# SCH_stmsheild_2026-06-30.net
KiCad netlist of a schematic drawn in EasyEDA
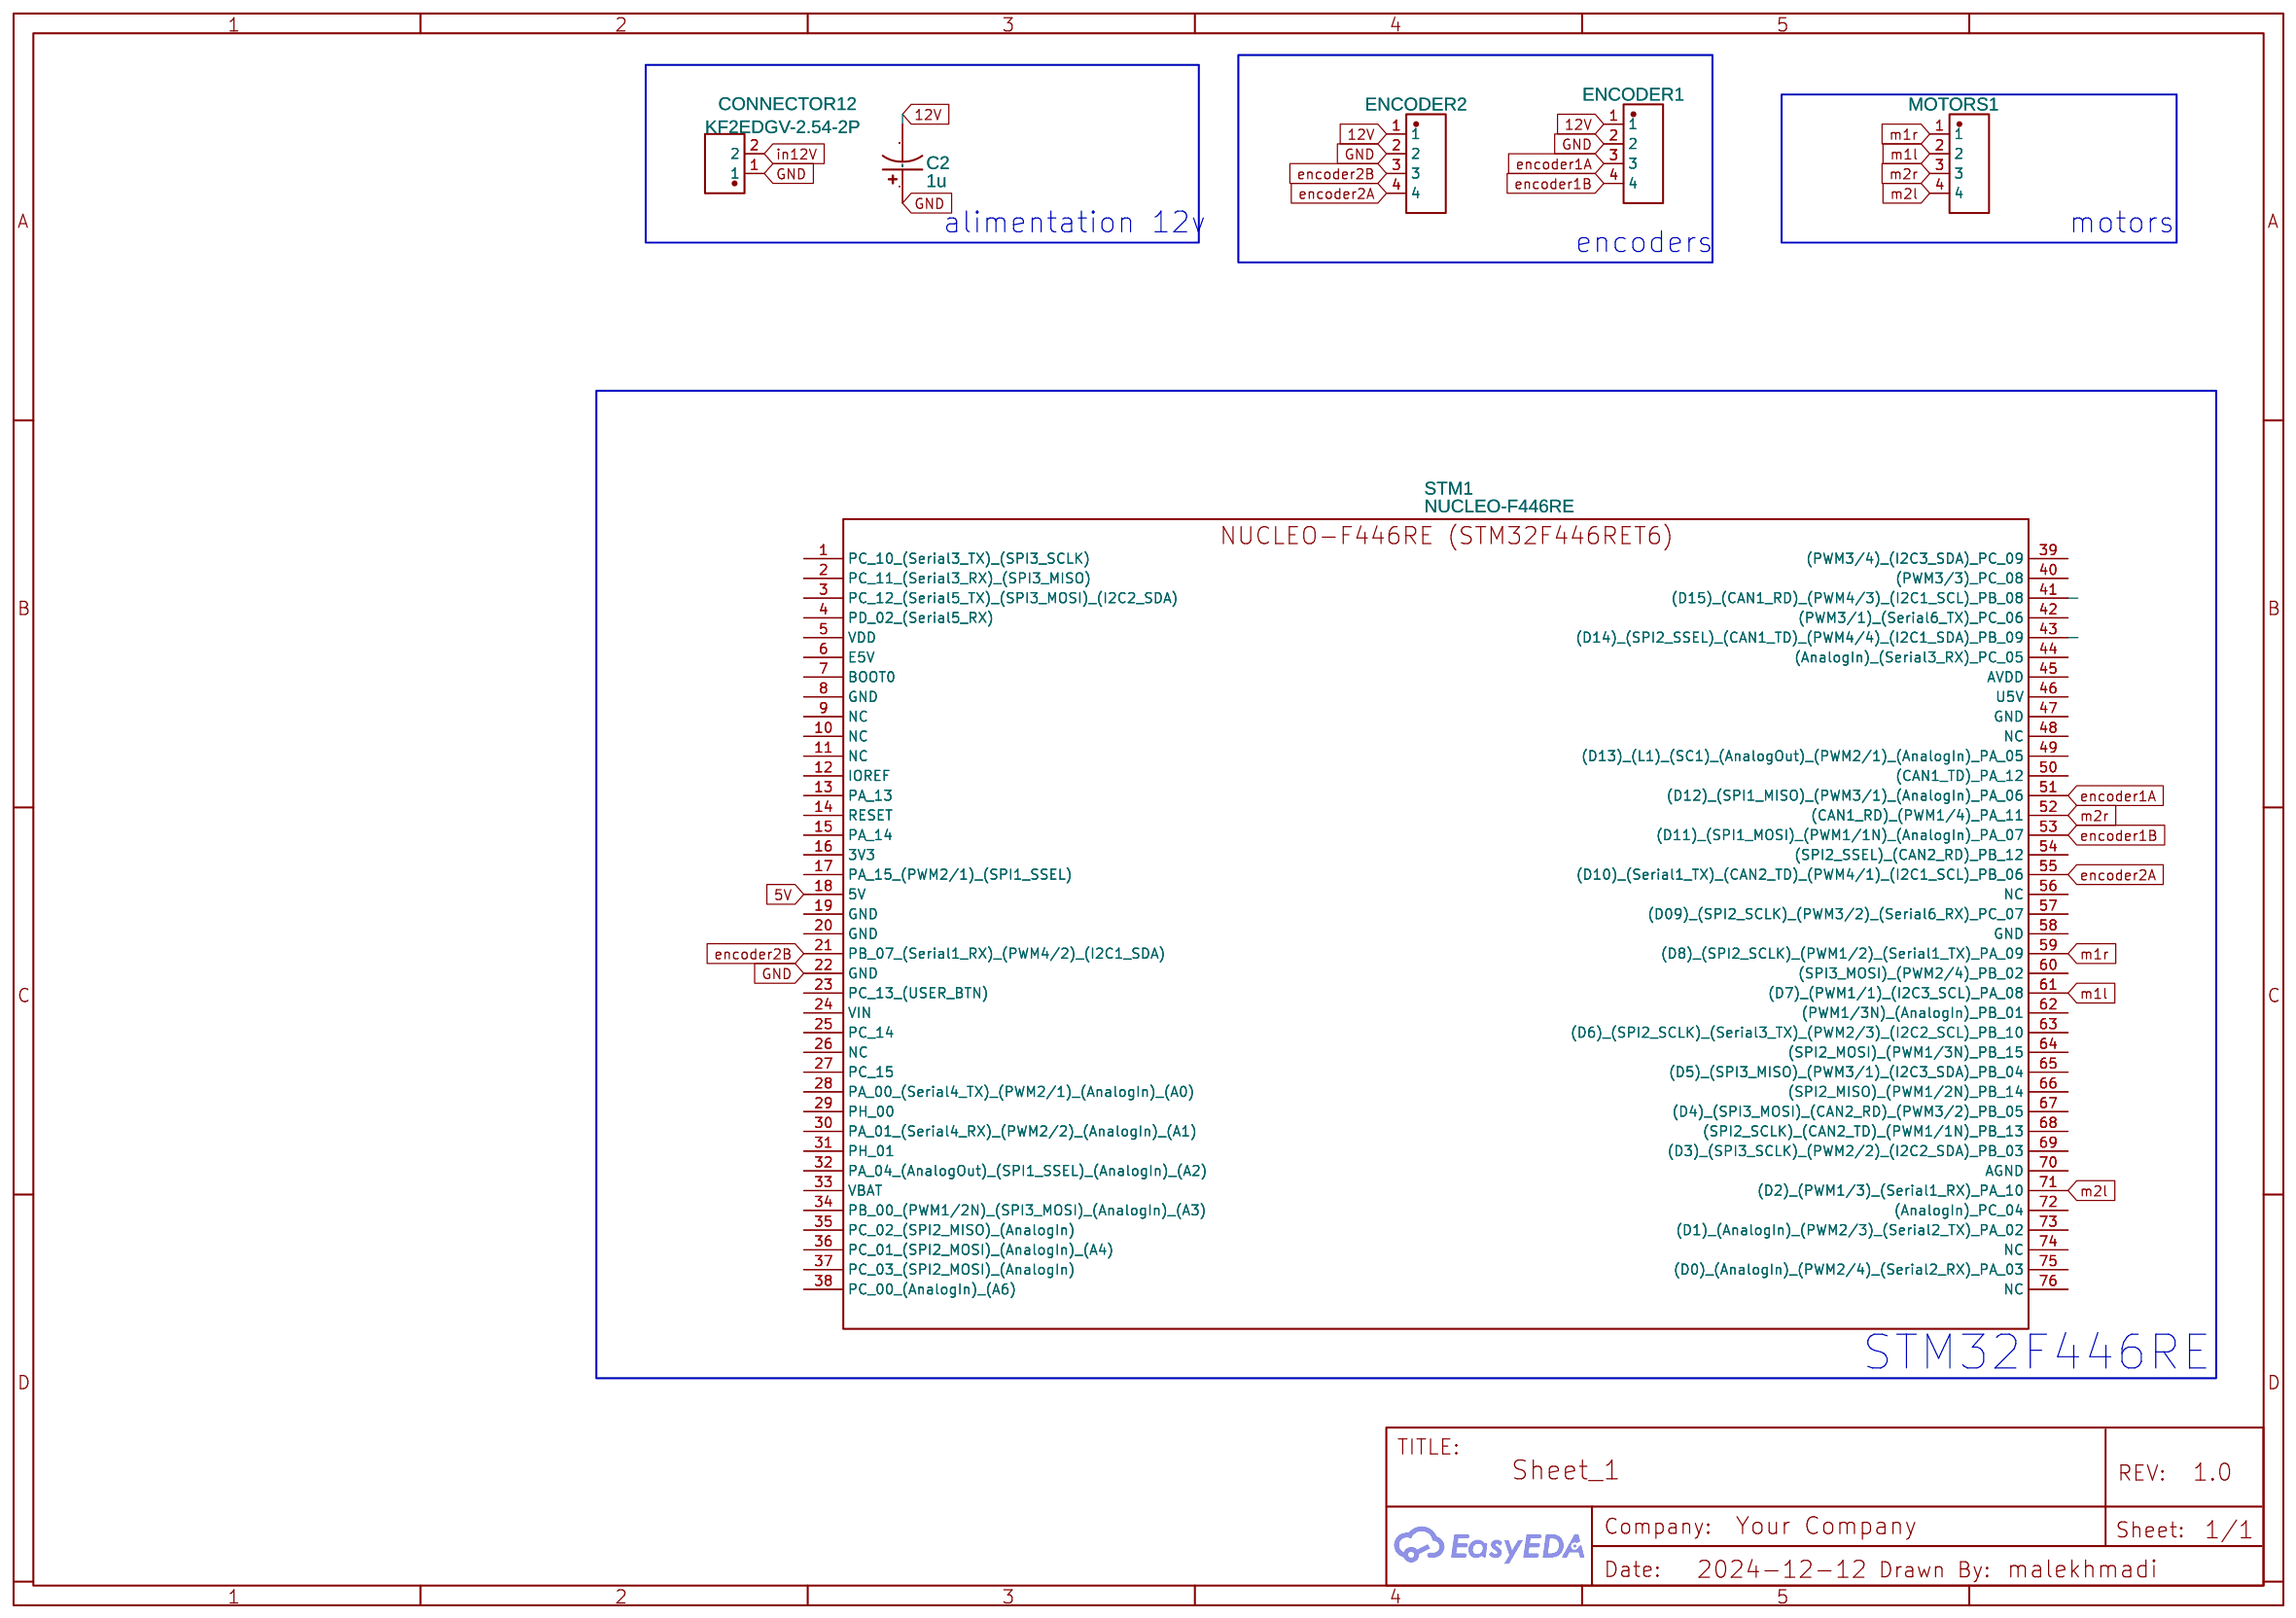
[diagram p0: schematic sheet]

(export (version "E")
  (design (tool "Eeschema 10.0.6"))
  (components
    (comp (ref "C2") (value "1u") (libsource (lib "") (part "CE_TH_D4.0×F1.5_US")))
    (comp (ref "CONNECTOR12")
      (value "KF2EDGV-2.54-2P")
      (fields (field (name "Manufacturer") "Cixi Kefa Elec"))
      (libsource (lib "") (part "KF2EDGV-2.54-2P"))
    )
    (comp (ref "ENCODER1")
      (value "HC-XHB-4A")
      (fields (field (name "Manufacturer") "HCTL(华灿天禄)"))
      (libsource (lib "") (part "HC-XHB-4A_1"))
    )
    (comp (ref "ENCODER2")
      (value "HC-XHB-4A")
      (fields (field (name "Manufacturer") "HCTL(华灿天禄)"))
      (libsource (lib "") (part "HC-XHB-4A_1"))
    )
    (comp (ref "MOTORS1")
      (value "HC-XHB-4A")
      (fields (field (name "Manufacturer") "HCTL(华灿天禄)"))
      (libsource (lib "") (part "HC-XHB-4A"))
    )
    (comp (ref "STM1") (value "NUCLEO-F446RE") (libsource (lib "") (part "NUCLEO-F446RE")))
  )
  (nets
    (net (code "1") (name "5V") (class "Default")
      (node (ref "STM1") (pin "18") (pinfunction "5V_18") (pintype "passive"))
    )
    (net (code "2") (name "12V") (class "Default")
      (node (ref "C2") (pin "2") (pinfunction "2_2") (pintype "unspecified"))
      (node (ref "ENCODER1") (pin "1") (pinfunction "1_1") (pintype "unspecified"))
      (node (ref "ENCODER2") (pin "1") (pinfunction "1_1") (pintype "unspecified"))
    )
    (net (code "3") (name "GND") (class "Default")
      (node (ref "C2") (pin "1") (pinfunction "1_1") (pintype "unspecified"))
      (node (ref "CONNECTOR12") (pin "1") (pinfunction "1_1") (pintype "unspecified"))
      (node (ref "ENCODER1") (pin "2") (pinfunction "2_2") (pintype "unspecified"))
      (node (ref "ENCODER2") (pin "2") (pinfunction "2_2") (pintype "unspecified"))
      (node (ref "STM1") (pin "22") (pinfunction "GND_22") (pintype "passive"))
    )
    (net (code "4") (name "encoder1A") (class "Default")
      (node (ref "ENCODER1") (pin "3") (pinfunction "3_3") (pintype "unspecified"))
      (node (ref "STM1") (pin "51") (pinfunction "(D12)_(SPI1_MISO)_(PWM3/1)_(AnalogIn)_PA_06_51") (pintype "bidirectional"))
    )
    (net (code "5") (name "encoder1B") (class "Default")
      (node (ref "ENCODER1") (pin "4") (pinfunction "4_4") (pintype "unspecified"))
      (node (ref "STM1") (pin "53") (pinfunction "(D11)_(SPI1_MOSI)_(PWM1/1N)_(AnalogIn)_PA_07_53") (pintype "bidirectional"))
    )
    (net (code "6") (name "encoder2A") (class "Default")
      (node (ref "ENCODER2") (pin "4") (pinfunction "4_4") (pintype "unspecified"))
      (node (ref "STM1") (pin "55") (pinfunction "(D10)_(Serial1_TX)_(CAN2_TD)_(PWM4/1)_(I2C1_SCL)_PB_06_55") (pintype "bidirectional"))
    )
    (net (code "7") (name "encoder2B") (class "Default")
      (node (ref "ENCODER2") (pin "3") (pinfunction "3_3") (pintype "unspecified"))
      (node (ref "STM1") (pin "21") (pinfunction "PB_07_(Serial1_RX)_(PWM4/2)_(I2C1_SDA)_21") (pintype "bidirectional"))
    )
    (net (code "8") (name "in12V") (class "Default")
      (node (ref "CONNECTOR12") (pin "2") (pinfunction "2_2") (pintype "unspecified"))
    )
    (net (code "9") (name "m1l") (class "Default")
      (node (ref "MOTORS1") (pin "2") (pinfunction "2_2") (pintype "unspecified"))
      (node (ref "STM1") (pin "61") (pinfunction "(D7)_(PWM1/1)_(I2C3_SCL)_PA_08_61") (pintype "bidirectional"))
    )
    (net (code "10") (name "m1r") (class "Default")
      (node (ref "MOTORS1") (pin "1") (pinfunction "1_1") (pintype "unspecified"))
      (node (ref "STM1") (pin "59") (pinfunction "(D8)_(SPI2_SCLK)_(PWM1/2)_(Serial1_TX)_PA_09_59") (pintype "bidirectional"))
    )
    (net (code "11") (name "m2l") (class "Default")
      (node (ref "MOTORS1") (pin "4") (pinfunction "4_4") (pintype "unspecified"))
      (node (ref "STM1") (pin "71") (pinfunction "(D2)_(PWM1/3)_(Serial1_RX)_PA_10_71") (pintype "bidirectional"))
    )
    (net (code "12") (name "m2r") (class "Default")
      (node (ref "MOTORS1") (pin "3") (pinfunction "3_3") (pintype "unspecified"))
      (node (ref "STM1") (pin "52") (pinfunction "(CAN1_RD)_(PWM1/4)_PA_11_52") (pintype "bidirectional"))
    )
    (net (code "13") (name "unconnected-(STM1-(AnalogIn)_(Serial3_RX)_PC_05-Pad44)") (class "Default")
      (node (ref "STM1") (pin "44") (pinfunction "(AnalogIn)_(Serial3_RX)_PC_05_44") (pintype "bidirectional"))
    )
    (net (code "14") (name "unconnected-(STM1-(AnalogIn)_PC_04-Pad72)") (class "Default")
      (node (ref "STM1") (pin "72") (pinfunction "(AnalogIn)_PC_04_72") (pintype "bidirectional"))
    )
    (net (code "15") (name "unconnected-(STM1-(CAN1_TD)_PA_12-Pad50)") (class "Default")
      (node (ref "STM1") (pin "50") (pinfunction "(CAN1_TD)_PA_12_50") (pintype "bidirectional"))
    )
    (net (code "16") (name "unconnected-(STM1-(D0)_(AnalogIn)_(PWM2{slash}4)_(Serial2_RX)_PA_03-Pad75)") (class "Default")
      (node (ref "STM1") (pin "75") (pinfunction "(D0)_(AnalogIn)_(PWM2/4)_(Serial2_RX)_PA_03_75") (pintype "bidirectional"))
    )
    (net (code "17") (name "unconnected-(STM1-(D1)_(AnalogIn)_(PWM2{slash}3)_(Serial2_TX)_PA_02-Pad73)") (class "Default")
      (node (ref "STM1") (pin "73") (pinfunction "(D1)_(AnalogIn)_(PWM2/3)_(Serial2_TX)_PA_02_73") (pintype "bidirectional"))
    )
    (net (code "18") (name "unconnected-(STM1-(D3)_(SPI3_SCLK)_(PWM2{slash}2)_(I2C2_SDA)_PB_03-Pad69)") (class "Default")
      (node (ref "STM1") (pin "69") (pinfunction "(D3)_(SPI3_SCLK)_(PWM2/2)_(I2C2_SDA)_PB_03_69") (pintype "bidirectional"))
    )
    (net (code "19") (name "unconnected-(STM1-(D4)_(SPI3_MOSI)_(CAN2_RD)_(PWM3{slash}2)_PB_05-Pad67)") (class "Default")
      (node (ref "STM1") (pin "67") (pinfunction "(D4)_(SPI3_MOSI)_(CAN2_RD)_(PWM3/2)_PB_05_67") (pintype "bidirectional"))
    )
    (net (code "20") (name "unconnected-(STM1-(D5)_(SPI3_MISO)_(PWM3{slash}1)_(I2C3_SDA)_PB_04-Pad65)") (class "Default")
      (node (ref "STM1") (pin "65") (pinfunction "(D5)_(SPI3_MISO)_(PWM3/1)_(I2C3_SDA)_PB_04_65") (pintype "bidirectional"))
    )
    (net (code "21") (name "unconnected-(STM1-(D6)_(SPI2_SCLK)_(Serial3_TX)_(PWM2{slash}3)_(I2C2_SCL)_PB_10-Pad63)") (class "Default")
      (node (ref "STM1") (pin "63") (pinfunction "(D6)_(SPI2_SCLK)_(Serial3_TX)_(PWM2/3)_(I2C2_SCL)_PB_10_63") (pintype "bidirectional"))
    )
    (net (code "22") (name "unconnected-(STM1-(D09)_(SPI2_SCLK)_(PWM3{slash}2)_(Serial6_RX)_PC_07-Pad57)") (class "Default")
      (node (ref "STM1") (pin "57") (pinfunction "(D09)_(SPI2_SCLK)_(PWM3/2)_(Serial6_RX)_PC_07_57") (pintype "bidirectional"))
    )
    (net (code "23") (name "unconnected-(STM1-(D13)_(L1)_(SC1)_(AnalogOut)_(PWM2{slash}1)_(AnalogIn)_PA_05-Pad49)") (class "Default")
      (node (ref "STM1") (pin "49") (pinfunction "(D13)_(L1)_(SC1)_(AnalogOut)_(PWM2/1)_(AnalogIn)_PA_05_49") (pintype "bidirectional"))
    )
    (net (code "24") (name "unconnected-(STM1-(D14)_(SPI2_SSEL)_(CAN1_TD)_(PWM4{slash}4)_(I2C1_SDA)_PB_09-Pad43)") (class "Default")
      (node (ref "STM1") (pin "43") (pinfunction "(D14)_(SPI2_SSEL)_(CAN1_TD)_(PWM4/4)_(I2C1_SDA)_PB_09_43") (pintype "bidirectional"))
    )
    (net (code "25") (name "unconnected-(STM1-(D15)_(CAN1_RD)_(PWM4{slash}3)_(I2C1_SCL)_PB_08-Pad41)") (class "Default")
      (node (ref "STM1") (pin "41") (pinfunction "(D15)_(CAN1_RD)_(PWM4/3)_(I2C1_SCL)_PB_08_41") (pintype "bidirectional"))
    )
    (net (code "26") (name "unconnected-(STM1-(PWM1{slash}3N)_(AnalogIn)_PB_01-Pad62)") (class "Default")
      (node (ref "STM1") (pin "62") (pinfunction "(PWM1/3N)_(AnalogIn)_PB_01_62") (pintype "bidirectional"))
    )
    (net (code "27") (name "unconnected-(STM1-(PWM3{slash}1)_(Serial6_TX)_PC_06-Pad42)") (class "Default")
      (node (ref "STM1") (pin "42") (pinfunction "(PWM3/1)_(Serial6_TX)_PC_06_42") (pintype "bidirectional"))
    )
    (net (code "28") (name "unconnected-(STM1-(PWM3{slash}3)_PC_08-Pad40)") (class "Default")
      (node (ref "STM1") (pin "40") (pinfunction "(PWM3/3)_PC_08_40") (pintype "bidirectional"))
    )
    (net (code "29") (name "unconnected-(STM1-(PWM3{slash}4)_(I2C3_SDA)_PC_09-Pad39)") (class "Default")
      (node (ref "STM1") (pin "39") (pinfunction "(PWM3/4)_(I2C3_SDA)_PC_09_39") (pintype "bidirectional"))
    )
    (net (code "30") (name "unconnected-(STM1-(SPI2_MISO)_(PWM1{slash}2N)_PB_14-Pad66)") (class "Default")
      (node (ref "STM1") (pin "66") (pinfunction "(SPI2_MISO)_(PWM1/2N)_PB_14_66") (pintype "bidirectional"))
    )
    (net (code "31") (name "unconnected-(STM1-(SPI2_MOSI)_(PWM1{slash}3N)_PB_15-Pad64)") (class "Default")
      (node (ref "STM1") (pin "64") (pinfunction "(SPI2_MOSI)_(PWM1/3N)_PB_15_64") (pintype "bidirectional"))
    )
    (net (code "32") (name "unconnected-(STM1-(SPI2_SCLK)_(CAN2_TD)_(PWM1{slash}1N)_PB_13-Pad68)") (class "Default")
      (node (ref "STM1") (pin "68") (pinfunction "(SPI2_SCLK)_(CAN2_TD)_(PWM1/1N)_PB_13_68") (pintype "bidirectional"))
    )
    (net (code "33") (name "unconnected-(STM1-(SPI2_SSEL)_(CAN2_RD)_PB_12-Pad54)") (class "Default")
      (node (ref "STM1") (pin "54") (pinfunction "(SPI2_SSEL)_(CAN2_RD)_PB_12_54") (pintype "bidirectional"))
    )
    (net (code "34") (name "unconnected-(STM1-(SPI3_MOSI)_(PWM2{slash}4)_PB_02-Pad60)") (class "Default")
      (node (ref "STM1") (pin "60") (pinfunction "(SPI3_MOSI)_(PWM2/4)_PB_02_60") (pintype "bidirectional"))
    )
    (net (code "35") (name "unconnected-(STM1-3V3-Pad16)") (class "Default")
      (node (ref "STM1") (pin "16") (pinfunction "3V3_16") (pintype "passive"))
    )
    (net (code "36") (name "unconnected-(STM1-AGND-Pad70)") (class "Default")
      (node (ref "STM1") (pin "70") (pinfunction "AGND_70") (pintype "passive"))
    )
    (net (code "37") (name "unconnected-(STM1-AVDD-Pad45)") (class "Default")
      (node (ref "STM1") (pin "45") (pinfunction "AVDD_45") (pintype "passive"))
    )
    (net (code "38") (name "unconnected-(STM1-BOOT0-Pad7)") (class "Default")
      (node (ref "STM1") (pin "7") (pinfunction "BOOT0_7") (pintype "unspecified"))
    )
    (net (code "39") (name "unconnected-(STM1-E5V-Pad6)") (class "Default")
      (node (ref "STM1") (pin "6") (pinfunction "E5V_6") (pintype "passive"))
    )
    (net (code "40") (name "unconnected-(STM1-GND-Pad8)") (class "Default")
      (node (ref "STM1") (pin "8") (pinfunction "GND_8") (pintype "unspecified"))
    )
    (net (code "41") (name "unconnected-(STM1-GND-Pad19)") (class "Default")
      (node (ref "STM1") (pin "19") (pinfunction "GND_19") (pintype "passive"))
    )
    (net (code "42") (name "unconnected-(STM1-GND-Pad20)") (class "Default")
      (node (ref "STM1") (pin "20") (pinfunction "GND_20") (pintype "passive"))
    )
    (net (code "43") (name "unconnected-(STM1-GND-Pad47)") (class "Default")
      (node (ref "STM1") (pin "47") (pinfunction "GND_47") (pintype "passive"))
    )
    (net (code "44") (name "unconnected-(STM1-GND-Pad58)") (class "Default")
      (node (ref "STM1") (pin "58") (pinfunction "GND_58") (pintype "passive"))
    )
    (net (code "45") (name "unconnected-(STM1-IOREF-Pad12)") (class "Default")
      (node (ref "STM1") (pin "12") (pinfunction "IOREF_12") (pintype "input"))
    )
    (net (code "46") (name "unconnected-(STM1-NC-Pad9)") (class "Default")
      (node (ref "STM1") (pin "9") (pinfunction "NC_9") (pintype "unspecified"))
    )
    (net (code "47") (name "unconnected-(STM1-NC-Pad10)") (class "Default")
      (node (ref "STM1") (pin "10") (pinfunction "NC_10") (pintype "unspecified"))
    )
    (net (code "48") (name "unconnected-(STM1-NC-Pad11)") (class "Default")
      (node (ref "STM1") (pin "11") (pinfunction "NC_11") (pintype "unspecified"))
    )
    (net (code "49") (name "unconnected-(STM1-NC-Pad26)") (class "Default")
      (node (ref "STM1") (pin "26") (pinfunction "NC_26") (pintype "unspecified"))
    )
    (net (code "50") (name "unconnected-(STM1-NC-Pad48)") (class "Default")
      (node (ref "STM1") (pin "48") (pinfunction "NC_48") (pintype "unspecified"))
    )
    (net (code "51") (name "unconnected-(STM1-NC-Pad56)") (class "Default")
      (node (ref "STM1") (pin "56") (pinfunction "NC_56") (pintype "unspecified"))
    )
    (net (code "52") (name "unconnected-(STM1-NC-Pad74)") (class "Default")
      (node (ref "STM1") (pin "74") (pinfunction "NC_74") (pintype "unspecified"))
    )
    (net (code "53") (name "unconnected-(STM1-NC-Pad76)") (class "Default")
      (node (ref "STM1") (pin "76") (pinfunction "NC_76") (pintype "unspecified"))
    )
    (net (code "54") (name "unconnected-(STM1-PA_00_(Serial4_TX)_(PWM2{slash}1)_(AnalogIn)_(A0)-Pad28)") (class "Default")
      (node (ref "STM1") (pin "28") (pinfunction "PA_00_(Serial4_TX)_(PWM2/1)_(AnalogIn)_(A0)_28") (pintype "bidirectional"))
    )
    (net (code "55") (name "unconnected-(STM1-PA_01_(Serial4_RX)_(PWM2{slash}2)_(AnalogIn)_(A1)-Pad30)") (class "Default")
      (node (ref "STM1") (pin "30") (pinfunction "PA_01_(Serial4_RX)_(PWM2/2)_(AnalogIn)_(A1)_30") (pintype "bidirectional"))
    )
    (net (code "56") (name "unconnected-(STM1-PA_04_(AnalogOut)_(SPI1_SSEL)_(AnalogIn)_(A2)-Pad32)") (class "Default")
      (node (ref "STM1") (pin "32") (pinfunction "PA_04_(AnalogOut)_(SPI1_SSEL)_(AnalogIn)_(A2)_32") (pintype "bidirectional"))
    )
    (net (code "57") (name "unconnected-(STM1-PA_13-Pad13)") (class "Default")
      (node (ref "STM1") (pin "13") (pinfunction "PA_13_13") (pintype "bidirectional"))
    )
    (net (code "58") (name "unconnected-(STM1-PA_14-Pad15)") (class "Default")
      (node (ref "STM1") (pin "15") (pinfunction "PA_14_15") (pintype "bidirectional"))
    )
    (net (code "59") (name "unconnected-(STM1-PA_15_(PWM2{slash}1)_(SPI1_SSEL)-Pad17)") (class "Default")
      (node (ref "STM1") (pin "17") (pinfunction "PA_15_(PWM2/1)_(SPI1_SSEL)_17") (pintype "bidirectional"))
    )
    (net (code "60") (name "unconnected-(STM1-PB_00_(PWM1{slash}2N)_(SPI3_MOSI)_(AnalogIn)_(A3)-Pad34)") (class "Default")
      (node (ref "STM1") (pin "34") (pinfunction "PB_00_(PWM1/2N)_(SPI3_MOSI)_(AnalogIn)_(A3)_34") (pintype "bidirectional"))
    )
    (net (code "61") (name "unconnected-(STM1-PC_00_(AnalogIn)_(A6)-Pad38)") (class "Default")
      (node (ref "STM1") (pin "38") (pinfunction "PC_00_(AnalogIn)_(A6)_38") (pintype "bidirectional"))
    )
    (net (code "62") (name "unconnected-(STM1-PC_01_(SPI2_MOSI)_(AnalogIn)_(A4)-Pad36)") (class "Default")
      (node (ref "STM1") (pin "36") (pinfunction "PC_01_(SPI2_MOSI)_(AnalogIn)_(A4)_36") (pintype "bidirectional"))
    )
    (net (code "63") (name "unconnected-(STM1-PC_02_(SPI2_MISO)_(AnalogIn)-Pad35)") (class "Default")
      (node (ref "STM1") (pin "35") (pinfunction "PC_02_(SPI2_MISO)_(AnalogIn)_35") (pintype "bidirectional"))
    )
    (net (code "64") (name "unconnected-(STM1-PC_03_(SPI2_MOSI)_(AnalogIn)-Pad37)") (class "Default")
      (node (ref "STM1") (pin "37") (pinfunction "PC_03_(SPI2_MOSI)_(AnalogIn)_37") (pintype "bidirectional"))
    )
    (net (code "65") (name "unconnected-(STM1-PC_10_(Serial3_TX)_(SPI3_SCLK)-Pad1)") (class "Default")
      (node (ref "STM1") (pin "1") (pinfunction "PC_10_(Serial3_TX)_(SPI3_SCLK)_1") (pintype "bidirectional"))
    )
    (net (code "66") (name "unconnected-(STM1-PC_11_(Serial3_RX)_(SPI3_MISO)-Pad2)") (class "Default")
      (node (ref "STM1") (pin "2") (pinfunction "PC_11_(Serial3_RX)_(SPI3_MISO)_2") (pintype "bidirectional"))
    )
    (net (code "67") (name "unconnected-(STM1-PC_12_(Serial5_TX)_(SPI3_MOSI)_(I2C2_SDA)-Pad3)") (class "Default")
      (node (ref "STM1") (pin "3") (pinfunction "PC_12_(Serial5_TX)_(SPI3_MOSI)_(I2C2_SDA)_3") (pintype "bidirectional"))
    )
    (net (code "68") (name "unconnected-(STM1-PC_13_(USER_BTN)-Pad23)") (class "Default")
      (node (ref "STM1") (pin "23") (pinfunction "PC_13_(USER_BTN)_23") (pintype "bidirectional"))
    )
    (net (code "69") (name "unconnected-(STM1-PC_14-Pad25)") (class "Default")
      (node (ref "STM1") (pin "25") (pinfunction "PC_14_25") (pintype "bidirectional"))
    )
    (net (code "70") (name "unconnected-(STM1-PC_15-Pad27)") (class "Default")
      (node (ref "STM1") (pin "27") (pinfunction "PC_15_27") (pintype "bidirectional"))
    )
    (net (code "71") (name "unconnected-(STM1-PD_02_(Serial5_RX)-Pad4)") (class "Default")
      (node (ref "STM1") (pin "4") (pinfunction "PD_02_(Serial5_RX)_4") (pintype "bidirectional"))
    )
    (net (code "72") (name "unconnected-(STM1-PH_00-Pad29)") (class "Default")
      (node (ref "STM1") (pin "29") (pinfunction "PH_00_29") (pintype "bidirectional"))
    )
    (net (code "73") (name "unconnected-(STM1-PH_01-Pad31)") (class "Default")
      (node (ref "STM1") (pin "31") (pinfunction "PH_01_31") (pintype "bidirectional"))
    )
    (net (code "74") (name "unconnected-(STM1-RESET-Pad14)") (class "Default")
      (node (ref "STM1") (pin "14") (pinfunction "RESET_14") (pintype "input"))
    )
    (net (code "75") (name "unconnected-(STM1-U5V-Pad46)") (class "Default")
      (node (ref "STM1") (pin "46") (pinfunction "U5V_46") (pintype "passive"))
    )
    (net (code "76") (name "unconnected-(STM1-VBAT-Pad33)") (class "Default")
      (node (ref "STM1") (pin "33") (pinfunction "VBAT_33") (pintype "passive"))
    )
    (net (code "77") (name "unconnected-(STM1-VDD-Pad5)") (class "Default")
      (node (ref "STM1") (pin "5") (pinfunction "VDD_5") (pintype "passive"))
    )
    (net (code "78") (name "unconnected-(STM1-VIN-Pad24)") (class "Default")
      (node (ref "STM1") (pin "24") (pinfunction "VIN_24") (pintype "passive"))
    )
  )
)
